# Matrix.net
KiCad netlist of a schematic drawn in Altium Designer
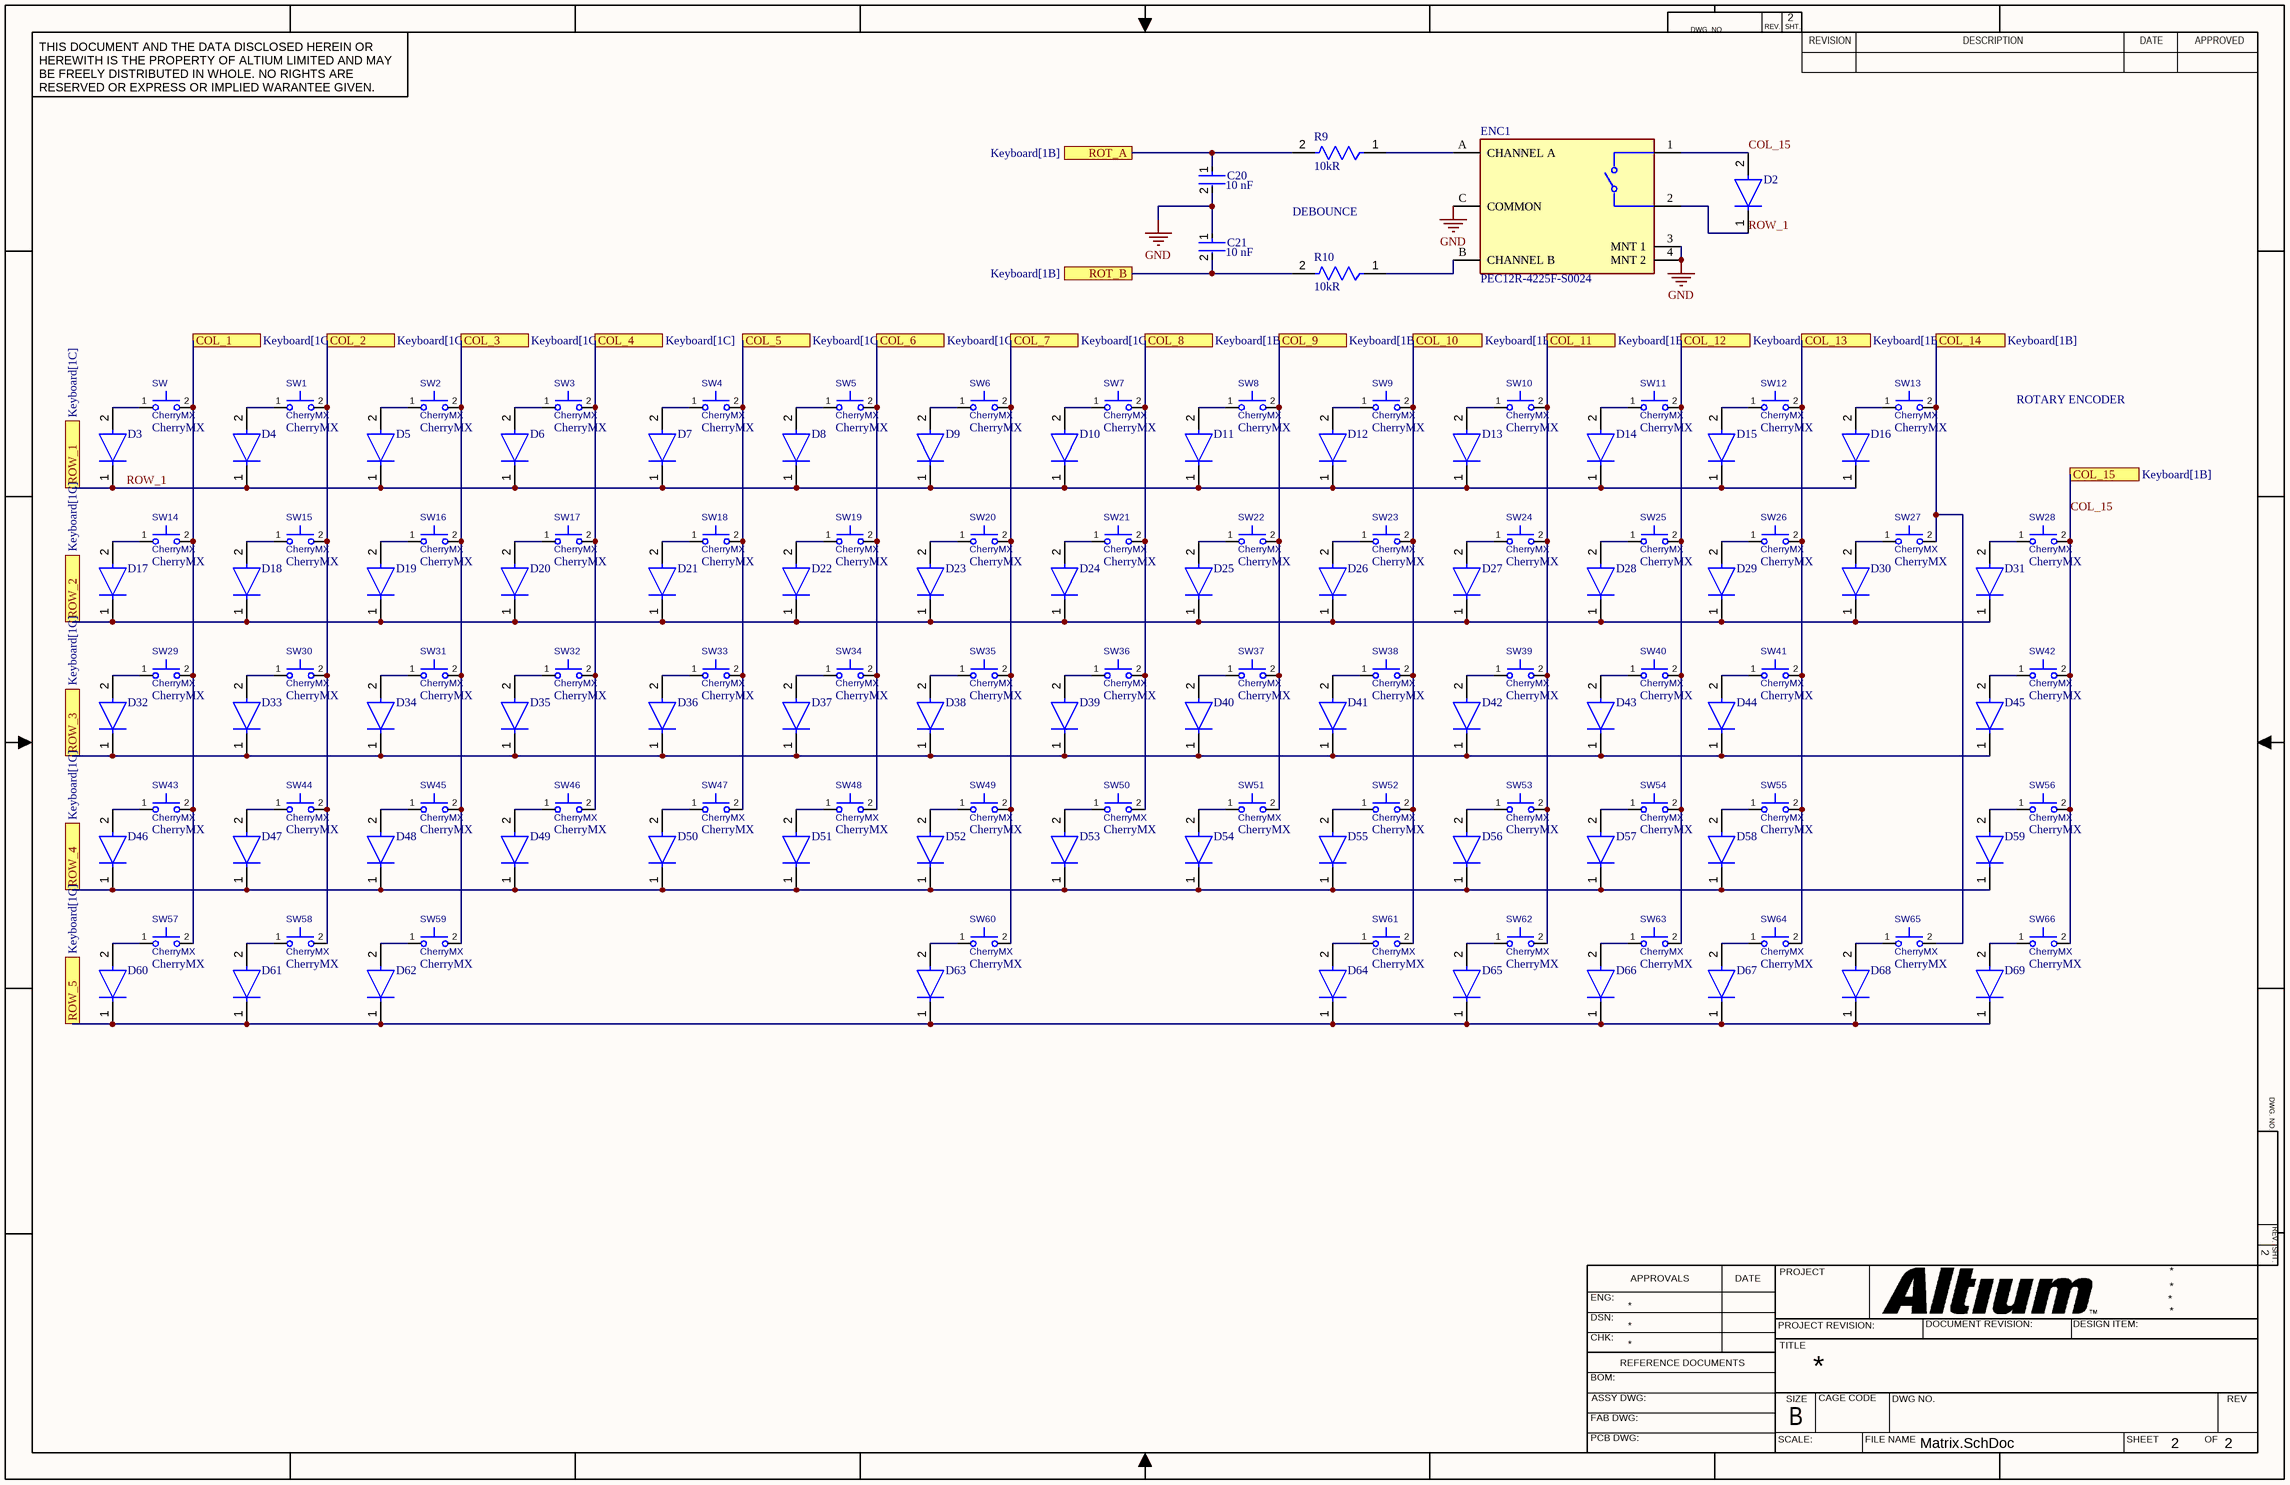
[diagram p0: Matrix.SchDoc]

(export (version "E")
  (design (tool "Eeschema 10.0.6"))
  (components
    (comp (ref "C20")
      (value "CC0603KRX7R9BB103")
      (footprint "FP-CC0603-DA-MFG")
      (description "CAP CER 10000PF 50V X7R 0603")
      (fields
        (field (name "TOLERANCE") "0.1")
        (field (name "MANUFACTURER") "YAGEO")
        (field (name "CAPACITANCE") "10 nF")
      )
      (libsource (lib "Altium Content Vault") (part "11868f565c42a9108669ba33697ecf6"))
    )
    (comp (ref "C21")
      (value "CC0603KRX7R9BB103")
      (footprint "FP-CC0603-DA-MFG")
      (description "CAP CER 10000PF 50V X7R 0603")
      (fields
        (field (name "TOLERANCE") "0.1")
        (field (name "MANUFACTURER") "YAGEO")
        (field (name "CAPACITANCE") "10 nF")
      )
      (libsource (lib "Altium Content Vault") (part "11868f565c42a9108669ba33697ecf6"))
    )
    (comp (ref "D2")
      (value "1N4148W-TP")
      (footprint "FP-SOD-123-IPC_A")
      (description "DIODE GEN PURP 100V 150MA SOD123")
      (libsource (lib "Altium Content Vault") (part "d7152d700b627762746794eb795d46e"))
    )
    (comp (ref "D3")
      (value "1N4148W-TP")
      (footprint "FP-SOD-123-IPC_A")
      (description "DIODE GEN PURP 100V 150MA SOD123")
      (libsource (lib "Altium Content Vault") (part "d7152d700b627762746794eb795d46e"))
    )
    (comp (ref "D4")
      (value "1N4148W-TP")
      (footprint "FP-SOD-123-IPC_A")
      (description "DIODE GEN PURP 100V 150MA SOD123")
      (libsource (lib "Altium Content Vault") (part "d7152d700b627762746794eb795d46e"))
    )
    (comp (ref "D5")
      (value "1N4148W-TP")
      (footprint "FP-SOD-123-IPC_A")
      (description "DIODE GEN PURP 100V 150MA SOD123")
      (libsource (lib "Altium Content Vault") (part "d7152d700b627762746794eb795d46e"))
    )
    (comp (ref "D6")
      (value "1N4148W-TP")
      (footprint "FP-SOD-123-IPC_A")
      (description "DIODE GEN PURP 100V 150MA SOD123")
      (libsource (lib "Altium Content Vault") (part "d7152d700b627762746794eb795d46e"))
    )
    (comp (ref "D7")
      (value "1N4148W-TP")
      (footprint "FP-SOD-123-IPC_A")
      (description "DIODE GEN PURP 100V 150MA SOD123")
      (libsource (lib "Altium Content Vault") (part "d7152d700b627762746794eb795d46e"))
    )
    (comp (ref "D8")
      (value "1N4148W-TP")
      (footprint "FP-SOD-123-IPC_A")
      (description "DIODE GEN PURP 100V 150MA SOD123")
      (libsource (lib "Altium Content Vault") (part "d7152d700b627762746794eb795d46e"))
    )
    (comp (ref "D9")
      (value "1N4148W-TP")
      (footprint "FP-SOD-123-IPC_A")
      (description "DIODE GEN PURP 100V 150MA SOD123")
      (libsource (lib "Altium Content Vault") (part "d7152d700b627762746794eb795d46e"))
    )
    (comp (ref "D10")
      (value "1N4148W-TP")
      (footprint "FP-SOD-123-IPC_A")
      (description "DIODE GEN PURP 100V 150MA SOD123")
      (libsource (lib "Altium Content Vault") (part "d7152d700b627762746794eb795d46e"))
    )
    (comp (ref "D11")
      (value "1N4148W-TP")
      (footprint "FP-SOD-123-IPC_A")
      (description "DIODE GEN PURP 100V 150MA SOD123")
      (libsource (lib "Altium Content Vault") (part "d7152d700b627762746794eb795d46e"))
    )
    (comp (ref "D12")
      (value "1N4148W-TP")
      (footprint "FP-SOD-123-IPC_A")
      (description "DIODE GEN PURP 100V 150MA SOD123")
      (libsource (lib "Altium Content Vault") (part "d7152d700b627762746794eb795d46e"))
    )
    (comp (ref "D13")
      (value "1N4148W-TP")
      (footprint "FP-SOD-123-IPC_A")
      (description "DIODE GEN PURP 100V 150MA SOD123")
      (libsource (lib "Altium Content Vault") (part "d7152d700b627762746794eb795d46e"))
    )
    (comp (ref "D14")
      (value "1N4148W-TP")
      (footprint "FP-SOD-123-IPC_A")
      (description "DIODE GEN PURP 100V 150MA SOD123")
      (libsource (lib "Altium Content Vault") (part "d7152d700b627762746794eb795d46e"))
    )
    (comp (ref "D15")
      (value "1N4148W-TP")
      (footprint "FP-SOD-123-IPC_A")
      (description "DIODE GEN PURP 100V 150MA SOD123")
      (libsource (lib "Altium Content Vault") (part "d7152d700b627762746794eb795d46e"))
    )
    (comp (ref "D16")
      (value "1N4148W-TP")
      (footprint "FP-SOD-123-IPC_A")
      (description "DIODE GEN PURP 100V 150MA SOD123")
      (libsource (lib "Altium Content Vault") (part "d7152d700b627762746794eb795d46e"))
    )
    (comp (ref "D17")
      (value "1N4148W-TP")
      (footprint "FP-SOD-123-IPC_A")
      (description "DIODE GEN PURP 100V 150MA SOD123")
      (libsource (lib "Altium Content Vault") (part "d7152d700b627762746794eb795d46e"))
    )
    (comp (ref "D18")
      (value "1N4148W-TP")
      (footprint "FP-SOD-123-IPC_A")
      (description "DIODE GEN PURP 100V 150MA SOD123")
      (libsource (lib "Altium Content Vault") (part "d7152d700b627762746794eb795d46e"))
    )
    (comp (ref "D19")
      (value "1N4148W-TP")
      (footprint "FP-SOD-123-IPC_A")
      (description "DIODE GEN PURP 100V 150MA SOD123")
      (libsource (lib "Altium Content Vault") (part "d7152d700b627762746794eb795d46e"))
    )
    (comp (ref "D20")
      (value "1N4148W-TP")
      (footprint "FP-SOD-123-IPC_A")
      (description "DIODE GEN PURP 100V 150MA SOD123")
      (libsource (lib "Altium Content Vault") (part "d7152d700b627762746794eb795d46e"))
    )
    (comp (ref "D21")
      (value "1N4148W-TP")
      (footprint "FP-SOD-123-IPC_A")
      (description "DIODE GEN PURP 100V 150MA SOD123")
      (libsource (lib "Altium Content Vault") (part "d7152d700b627762746794eb795d46e"))
    )
    (comp (ref "D22")
      (value "1N4148W-TP")
      (footprint "FP-SOD-123-IPC_A")
      (description "DIODE GEN PURP 100V 150MA SOD123")
      (libsource (lib "Altium Content Vault") (part "d7152d700b627762746794eb795d46e"))
    )
    (comp (ref "D23")
      (value "1N4148W-TP")
      (footprint "FP-SOD-123-IPC_A")
      (description "DIODE GEN PURP 100V 150MA SOD123")
      (libsource (lib "Altium Content Vault") (part "d7152d700b627762746794eb795d46e"))
    )
    (comp (ref "D24")
      (value "1N4148W-TP")
      (footprint "FP-SOD-123-IPC_A")
      (description "DIODE GEN PURP 100V 150MA SOD123")
      (libsource (lib "Altium Content Vault") (part "d7152d700b627762746794eb795d46e"))
    )
    (comp (ref "D25")
      (value "1N4148W-TP")
      (footprint "FP-SOD-123-IPC_A")
      (description "DIODE GEN PURP 100V 150MA SOD123")
      (libsource (lib "Altium Content Vault") (part "d7152d700b627762746794eb795d46e"))
    )
    (comp (ref "D26")
      (value "1N4148W-TP")
      (footprint "FP-SOD-123-IPC_A")
      (description "DIODE GEN PURP 100V 150MA SOD123")
      (libsource (lib "Altium Content Vault") (part "d7152d700b627762746794eb795d46e"))
    )
    (comp (ref "D27")
      (value "1N4148W-TP")
      (footprint "FP-SOD-123-IPC_A")
      (description "DIODE GEN PURP 100V 150MA SOD123")
      (libsource (lib "Altium Content Vault") (part "d7152d700b627762746794eb795d46e"))
    )
    (comp (ref "D28")
      (value "1N4148W-TP")
      (footprint "FP-SOD-123-IPC_A")
      (description "DIODE GEN PURP 100V 150MA SOD123")
      (libsource (lib "Altium Content Vault") (part "d7152d700b627762746794eb795d46e"))
    )
    (comp (ref "D29")
      (value "1N4148W-TP")
      (footprint "FP-SOD-123-IPC_A")
      (description "DIODE GEN PURP 100V 150MA SOD123")
      (libsource (lib "Altium Content Vault") (part "d7152d700b627762746794eb795d46e"))
    )
    (comp (ref "D30")
      (value "1N4148W-TP")
      (footprint "FP-SOD-123-IPC_A")
      (description "DIODE GEN PURP 100V 150MA SOD123")
      (libsource (lib "Altium Content Vault") (part "d7152d700b627762746794eb795d46e"))
    )
    (comp (ref "D31")
      (value "1N4148W-TP")
      (footprint "FP-SOD-123-IPC_A")
      (description "DIODE GEN PURP 100V 150MA SOD123")
      (libsource (lib "Altium Content Vault") (part "d7152d700b627762746794eb795d46e"))
    )
    (comp (ref "D32")
      (value "1N4148W-TP")
      (footprint "FP-SOD-123-IPC_A")
      (description "DIODE GEN PURP 100V 150MA SOD123")
      (libsource (lib "Altium Content Vault") (part "d7152d700b627762746794eb795d46e"))
    )
    (comp (ref "D33")
      (value "1N4148W-TP")
      (footprint "FP-SOD-123-IPC_A")
      (description "DIODE GEN PURP 100V 150MA SOD123")
      (libsource (lib "Altium Content Vault") (part "d7152d700b627762746794eb795d46e"))
    )
    (comp (ref "D34")
      (value "1N4148W-TP")
      (footprint "FP-SOD-123-IPC_A")
      (description "DIODE GEN PURP 100V 150MA SOD123")
      (libsource (lib "Altium Content Vault") (part "d7152d700b627762746794eb795d46e"))
    )
    (comp (ref "D35")
      (value "1N4148W-TP")
      (footprint "FP-SOD-123-IPC_A")
      (description "DIODE GEN PURP 100V 150MA SOD123")
      (libsource (lib "Altium Content Vault") (part "d7152d700b627762746794eb795d46e"))
    )
    (comp (ref "D36")
      (value "1N4148W-TP")
      (footprint "FP-SOD-123-IPC_A")
      (description "DIODE GEN PURP 100V 150MA SOD123")
      (libsource (lib "Altium Content Vault") (part "d7152d700b627762746794eb795d46e"))
    )
    (comp (ref "D37")
      (value "1N4148W-TP")
      (footprint "FP-SOD-123-IPC_A")
      (description "DIODE GEN PURP 100V 150MA SOD123")
      (libsource (lib "Altium Content Vault") (part "d7152d700b627762746794eb795d46e"))
    )
    (comp (ref "D38")
      (value "1N4148W-TP")
      (footprint "FP-SOD-123-IPC_A")
      (description "DIODE GEN PURP 100V 150MA SOD123")
      (libsource (lib "Altium Content Vault") (part "d7152d700b627762746794eb795d46e"))
    )
    (comp (ref "D39")
      (value "1N4148W-TP")
      (footprint "FP-SOD-123-IPC_A")
      (description "DIODE GEN PURP 100V 150MA SOD123")
      (libsource (lib "Altium Content Vault") (part "d7152d700b627762746794eb795d46e"))
    )
    (comp (ref "D40")
      (value "1N4148W-TP")
      (footprint "FP-SOD-123-IPC_A")
      (description "DIODE GEN PURP 100V 150MA SOD123")
      (libsource (lib "Altium Content Vault") (part "d7152d700b627762746794eb795d46e"))
    )
    (comp (ref "D41")
      (value "1N4148W-TP")
      (footprint "FP-SOD-123-IPC_A")
      (description "DIODE GEN PURP 100V 150MA SOD123")
      (libsource (lib "Altium Content Vault") (part "d7152d700b627762746794eb795d46e"))
    )
    (comp (ref "D42")
      (value "1N4148W-TP")
      (footprint "FP-SOD-123-IPC_A")
      (description "DIODE GEN PURP 100V 150MA SOD123")
      (libsource (lib "Altium Content Vault") (part "d7152d700b627762746794eb795d46e"))
    )
    (comp (ref "D43")
      (value "1N4148W-TP")
      (footprint "FP-SOD-123-IPC_A")
      (description "DIODE GEN PURP 100V 150MA SOD123")
      (libsource (lib "Altium Content Vault") (part "d7152d700b627762746794eb795d46e"))
    )
    (comp (ref "D44")
      (value "1N4148W-TP")
      (footprint "FP-SOD-123-IPC_A")
      (description "DIODE GEN PURP 100V 150MA SOD123")
      (libsource (lib "Altium Content Vault") (part "d7152d700b627762746794eb795d46e"))
    )
    (comp (ref "D45")
      (value "1N4148W-TP")
      (footprint "FP-SOD-123-IPC_A")
      (description "DIODE GEN PURP 100V 150MA SOD123")
      (libsource (lib "Altium Content Vault") (part "d7152d700b627762746794eb795d46e"))
    )
    (comp (ref "D46")
      (value "1N4148W-TP")
      (footprint "FP-SOD-123-IPC_A")
      (description "DIODE GEN PURP 100V 150MA SOD123")
      (libsource (lib "Altium Content Vault") (part "d7152d700b627762746794eb795d46e"))
    )
    (comp (ref "D47")
      (value "1N4148W-TP")
      (footprint "FP-SOD-123-IPC_A")
      (description "DIODE GEN PURP 100V 150MA SOD123")
      (libsource (lib "Altium Content Vault") (part "d7152d700b627762746794eb795d46e"))
    )
    (comp (ref "D48")
      (value "1N4148W-TP")
      (footprint "FP-SOD-123-IPC_A")
      (description "DIODE GEN PURP 100V 150MA SOD123")
      (libsource (lib "Altium Content Vault") (part "d7152d700b627762746794eb795d46e"))
    )
    (comp (ref "D49")
      (value "1N4148W-TP")
      (footprint "FP-SOD-123-IPC_A")
      (description "DIODE GEN PURP 100V 150MA SOD123")
      (libsource (lib "Altium Content Vault") (part "d7152d700b627762746794eb795d46e"))
    )
    (comp (ref "D50")
      (value "1N4148W-TP")
      (footprint "FP-SOD-123-IPC_A")
      (description "DIODE GEN PURP 100V 150MA SOD123")
      (libsource (lib "Altium Content Vault") (part "d7152d700b627762746794eb795d46e"))
    )
    (comp (ref "D51")
      (value "1N4148W-TP")
      (footprint "FP-SOD-123-IPC_A")
      (description "DIODE GEN PURP 100V 150MA SOD123")
      (libsource (lib "Altium Content Vault") (part "d7152d700b627762746794eb795d46e"))
    )
    (comp (ref "D52")
      (value "1N4148W-TP")
      (footprint "FP-SOD-123-IPC_A")
      (description "DIODE GEN PURP 100V 150MA SOD123")
      (libsource (lib "Altium Content Vault") (part "d7152d700b627762746794eb795d46e"))
    )
    (comp (ref "D53")
      (value "1N4148W-TP")
      (footprint "FP-SOD-123-IPC_A")
      (description "DIODE GEN PURP 100V 150MA SOD123")
      (libsource (lib "Altium Content Vault") (part "d7152d700b627762746794eb795d46e"))
    )
    (comp (ref "D54")
      (value "1N4148W-TP")
      (footprint "FP-SOD-123-IPC_A")
      (description "DIODE GEN PURP 100V 150MA SOD123")
      (libsource (lib "Altium Content Vault") (part "d7152d700b627762746794eb795d46e"))
    )
    (comp (ref "D55")
      (value "1N4148W-TP")
      (footprint "FP-SOD-123-IPC_A")
      (description "DIODE GEN PURP 100V 150MA SOD123")
      (libsource (lib "Altium Content Vault") (part "d7152d700b627762746794eb795d46e"))
    )
    (comp (ref "D56")
      (value "1N4148W-TP")
      (footprint "FP-SOD-123-IPC_A")
      (description "DIODE GEN PURP 100V 150MA SOD123")
      (libsource (lib "Altium Content Vault") (part "d7152d700b627762746794eb795d46e"))
    )
    (comp (ref "D57")
      (value "1N4148W-TP")
      (footprint "FP-SOD-123-IPC_A")
      (description "DIODE GEN PURP 100V 150MA SOD123")
      (libsource (lib "Altium Content Vault") (part "d7152d700b627762746794eb795d46e"))
    )
    (comp (ref "D58")
      (value "1N4148W-TP")
      (footprint "FP-SOD-123-IPC_A")
      (description "DIODE GEN PURP 100V 150MA SOD123")
      (libsource (lib "Altium Content Vault") (part "d7152d700b627762746794eb795d46e"))
    )
    (comp (ref "D59")
      (value "1N4148W-TP")
      (footprint "FP-SOD-123-IPC_A")
      (description "DIODE GEN PURP 100V 150MA SOD123")
      (libsource (lib "Altium Content Vault") (part "d7152d700b627762746794eb795d46e"))
    )
    (comp (ref "D60")
      (value "1N4148W-TP")
      (footprint "FP-SOD-123-IPC_A")
      (description "DIODE GEN PURP 100V 150MA SOD123")
      (libsource (lib "Altium Content Vault") (part "d7152d700b627762746794eb795d46e"))
    )
    (comp (ref "D61")
      (value "1N4148W-TP")
      (footprint "FP-SOD-123-IPC_A")
      (description "DIODE GEN PURP 100V 150MA SOD123")
      (libsource (lib "Altium Content Vault") (part "d7152d700b627762746794eb795d46e"))
    )
    (comp (ref "D62")
      (value "1N4148W-TP")
      (footprint "FP-SOD-123-IPC_A")
      (description "DIODE GEN PURP 100V 150MA SOD123")
      (libsource (lib "Altium Content Vault") (part "d7152d700b627762746794eb795d46e"))
    )
    (comp (ref "D63")
      (value "1N4148W-TP")
      (footprint "FP-SOD-123-IPC_A")
      (description "DIODE GEN PURP 100V 150MA SOD123")
      (libsource (lib "Altium Content Vault") (part "d7152d700b627762746794eb795d46e"))
    )
    (comp (ref "D64")
      (value "1N4148W-TP")
      (footprint "FP-SOD-123-IPC_A")
      (description "DIODE GEN PURP 100V 150MA SOD123")
      (libsource (lib "Altium Content Vault") (part "d7152d700b627762746794eb795d46e"))
    )
    (comp (ref "D65")
      (value "1N4148W-TP")
      (footprint "FP-SOD-123-IPC_A")
      (description "DIODE GEN PURP 100V 150MA SOD123")
      (libsource (lib "Altium Content Vault") (part "d7152d700b627762746794eb795d46e"))
    )
    (comp (ref "D66")
      (value "1N4148W-TP")
      (footprint "FP-SOD-123-IPC_A")
      (description "DIODE GEN PURP 100V 150MA SOD123")
      (libsource (lib "Altium Content Vault") (part "d7152d700b627762746794eb795d46e"))
    )
    (comp (ref "D67")
      (value "1N4148W-TP")
      (footprint "FP-SOD-123-IPC_A")
      (description "DIODE GEN PURP 100V 150MA SOD123")
      (libsource (lib "Altium Content Vault") (part "d7152d700b627762746794eb795d46e"))
    )
    (comp (ref "D68")
      (value "1N4148W-TP")
      (footprint "FP-SOD-123-IPC_A")
      (description "DIODE GEN PURP 100V 150MA SOD123")
      (libsource (lib "Altium Content Vault") (part "d7152d700b627762746794eb795d46e"))
    )
    (comp (ref "D69")
      (value "1N4148W-TP")
      (footprint "FP-SOD-123-IPC_A")
      (description "DIODE GEN PURP 100V 150MA SOD123")
      (libsource (lib "Altium Content Vault") (part "d7152d700b627762746794eb795d46e"))
    )
    (comp (ref "ENC1")
      (value "PEC12R-4225F-S0024")
      (footprint "FP-PEC12R-4225F-S0024-MFG")
      (description "ROTARY ENCODER MECHANICAL 24PPR")
      (libsource (lib "Altium Content Vault") (part "084942c7348c54a7e5fe2df5ed54478"))
    )
    (comp (ref "R9")
      (value "RC0402JR-0710KL")
      (footprint "FP-RC0402-0_4-IPC_C")
      (description "RES 10K OHM 5% 1/16W 0402")
      (fields (field (name "RESISTANCE") "10kR") (field (name "TOLERANCE") "5%"))
      (libsource (lib "Altium Content Vault") (part "1029c3af85768c4190bb7ad29bc67b5"))
    )
    (comp (ref "R10")
      (value "RC0402JR-0710KL")
      (footprint "FP-RC0402-0_4-IPC_C")
      (description "RES 10K OHM 5% 1/16W 0402")
      (fields (field (name "RESISTANCE") "10kR") (field (name "TOLERANCE") "5%"))
      (libsource (lib "Altium Content Vault") (part "1029c3af85768c4190bb7ad29bc67b5"))
    )
    (comp (ref "SW")
      (value "CherryMX")
      (footprint "CherryMX-Footprint-1")
      (description "Cherry Switch 1U")
      (fields (field (name "ALTIUM_VALUE") "CherryMX"))
      (libsource (lib "Brian Tan") (part "CherryMX"))
    )
    (comp (ref "SW1")
      (value "CherryMX")
      (footprint "CherryMX-Footprint-1")
      (description "Cherry Switch 1U")
      (fields (field (name "ALTIUM_VALUE") "CherryMX"))
      (libsource (lib "Brian Tan") (part "CherryMX"))
    )
    (comp (ref "SW2")
      (value "CherryMX")
      (footprint "CherryMX-Footprint-1")
      (description "Cherry Switch 1U")
      (fields (field (name "ALTIUM_VALUE") "CherryMX"))
      (libsource (lib "Brian Tan") (part "CherryMX"))
    )
    (comp (ref "SW3")
      (value "CherryMX")
      (footprint "CherryMX-Footprint-1")
      (description "Cherry Switch 1U")
      (fields (field (name "ALTIUM_VALUE") "CherryMX"))
      (libsource (lib "Brian Tan") (part "CherryMX"))
    )
    (comp (ref "SW4")
      (value "CherryMX")
      (footprint "CherryMX-Footprint-1")
      (description "Cherry Switch 1U")
      (fields (field (name "ALTIUM_VALUE") "CherryMX"))
      (libsource (lib "Brian Tan") (part "CherryMX"))
    )
    (comp (ref "SW5")
      (value "CherryMX")
      (footprint "CherryMX-Footprint-1")
      (description "Cherry Switch 1U")
      (fields (field (name "ALTIUM_VALUE") "CherryMX"))
      (libsource (lib "Brian Tan") (part "CherryMX"))
    )
    (comp (ref "SW6")
      (value "CherryMX")
      (footprint "CherryMX-Footprint-1")
      (description "Cherry Switch 1U")
      (fields (field (name "ALTIUM_VALUE") "CherryMX"))
      (libsource (lib "Brian Tan") (part "CherryMX"))
    )
    (comp (ref "SW7")
      (value "CherryMX")
      (footprint "CherryMX-Footprint-1")
      (description "Cherry Switch 1U")
      (fields (field (name "ALTIUM_VALUE") "CherryMX"))
      (libsource (lib "Brian Tan") (part "CherryMX"))
    )
    (comp (ref "SW8")
      (value "CherryMX")
      (footprint "CherryMX-Footprint-1")
      (description "Cherry Switch 1U")
      (fields (field (name "ALTIUM_VALUE") "CherryMX"))
      (libsource (lib "Brian Tan") (part "CherryMX"))
    )
    (comp (ref "SW9")
      (value "CherryMX")
      (footprint "CherryMX-Footprint-1")
      (description "Cherry Switch 1U")
      (fields (field (name "ALTIUM_VALUE") "CherryMX"))
      (libsource (lib "Brian Tan") (part "CherryMX"))
    )
    (comp (ref "SW10")
      (value "CherryMX")
      (footprint "CherryMX-Footprint-1")
      (description "Cherry Switch 1U")
      (fields (field (name "ALTIUM_VALUE") "CherryMX"))
      (libsource (lib "Brian Tan") (part "CherryMX"))
    )
    (comp (ref "SW11")
      (value "CherryMX")
      (footprint "CherryMX-Footprint-1")
      (description "Cherry Switch 1U")
      (fields (field (name "ALTIUM_VALUE") "CherryMX"))
      (libsource (lib "Brian Tan") (part "CherryMX"))
    )
    (comp (ref "SW12")
      (value "CherryMX")
      (footprint "CherryMX-Footprint-1")
      (description "Cherry Switch 1U")
      (fields (field (name "ALTIUM_VALUE") "CherryMX"))
      (libsource (lib "Brian Tan") (part "CherryMX"))
    )
    (comp (ref "SW13")
      (value "CherryMX")
      (footprint "CherryMX-Footprint-1")
      (description "Cherry Switch 1U")
      (fields (field (name "ALTIUM_VALUE") "CherryMX"))
      (libsource (lib "Brian Tan") (part "CherryMX"))
    )
    (comp (ref "SW14")
      (value "CherryMX")
      (footprint "CherryMX-Footprint-1")
      (description "Cherry Switch 1U")
      (fields (field (name "ALTIUM_VALUE") "CherryMX"))
      (libsource (lib "Brian Tan") (part "CherryMX"))
    )
    (comp (ref "SW15")
      (value "CherryMX")
      (footprint "CherryMX-Footprint-1")
      (description "Cherry Switch 1U")
      (fields (field (name "ALTIUM_VALUE") "CherryMX"))
      (libsource (lib "Brian Tan") (part "CherryMX"))
    )
    (comp (ref "SW16")
      (value "CherryMX")
      (footprint "CherryMX-Footprint-1")
      (description "Cherry Switch 1U")
      (fields (field (name "ALTIUM_VALUE") "CherryMX"))
      (libsource (lib "Brian Tan") (part "CherryMX"))
    )
    (comp (ref "SW17")
      (value "CherryMX")
      (footprint "CherryMX-Footprint-1")
      (description "Cherry Switch 1U")
      (fields (field (name "ALTIUM_VALUE") "CherryMX"))
      (libsource (lib "Brian Tan") (part "CherryMX"))
    )
    (comp (ref "SW18")
      (value "CherryMX")
      (footprint "CherryMX-Footprint-1")
      (description "Cherry Switch 1U")
      (fields (field (name "ALTIUM_VALUE") "CherryMX"))
      (libsource (lib "Brian Tan") (part "CherryMX"))
    )
    (comp (ref "SW19")
      (value "CherryMX")
      (footprint "CherryMX-Footprint-1")
      (description "Cherry Switch 1U")
      (fields (field (name "ALTIUM_VALUE") "CherryMX"))
      (libsource (lib "Brian Tan") (part "CherryMX"))
    )
    (comp (ref "SW20")
      (value "CherryMX")
      (footprint "CherryMX-Footprint-1")
      (description "Cherry Switch 1U")
      (fields (field (name "ALTIUM_VALUE") "CherryMX"))
      (libsource (lib "Brian Tan") (part "CherryMX"))
    )
    (comp (ref "SW21")
      (value "CherryMX")
      (footprint "CherryMX-Footprint-1")
      (description "Cherry Switch 1U")
      (fields (field (name "ALTIUM_VALUE") "CherryMX"))
      (libsource (lib "Brian Tan") (part "CherryMX"))
    )
    (comp (ref "SW22")
      (value "CherryMX")
      (footprint "CherryMX-Footprint-1")
      (description "Cherry Switch 1U")
      (fields (field (name "ALTIUM_VALUE") "CherryMX"))
      (libsource (lib "Brian Tan") (part "CherryMX"))
    )
    (comp (ref "SW23")
      (value "CherryMX")
      (footprint "CherryMX-Footprint-1")
      (description "Cherry Switch 1U")
      (fields (field (name "ALTIUM_VALUE") "CherryMX"))
      (libsource (lib "Brian Tan") (part "CherryMX"))
    )
    (comp (ref "SW24")
      (value "CherryMX")
      (footprint "CherryMX-Footprint-1")
      (description "Cherry Switch 1U")
      (fields (field (name "ALTIUM_VALUE") "CherryMX"))
      (libsource (lib "Brian Tan") (part "CherryMX"))
    )
    (comp (ref "SW25")
      (value "CherryMX")
      (footprint "CherryMX-Footprint-1")
      (description "Cherry Switch 1U")
      (fields (field (name "ALTIUM_VALUE") "CherryMX"))
      (libsource (lib "Brian Tan") (part "CherryMX"))
    )
    (comp (ref "SW26")
      (value "CherryMX")
      (footprint "CherryMX-Footprint-1")
      (description "Cherry Switch 1U")
      (fields (field (name "ALTIUM_VALUE") "CherryMX"))
      (libsource (lib "Brian Tan") (part "CherryMX"))
    )
    (comp (ref "SW27")
      (value "CherryMX")
      (footprint "CherryMX-Footprint-1")
      (description "Cherry Switch 1U")
      (fields (field (name "ALTIUM_VALUE") "CherryMX"))
      (libsource (lib "Brian Tan") (part "CherryMX"))
    )
    (comp (ref "SW28")
      (value "CherryMX")
      (footprint "CherryMX-Footprint-1")
      (description "Cherry Switch 1U")
      (fields (field (name "ALTIUM_VALUE") "CherryMX"))
      (libsource (lib "Brian Tan") (part "CherryMX"))
    )
    (comp (ref "SW29")
      (value "CherryMX")
      (footprint "CherryMX-Footprint-1")
      (description "Cherry Switch 1U")
      (fields (field (name "ALTIUM_VALUE") "CherryMX"))
      (libsource (lib "Brian Tan") (part "CherryMX"))
    )
    (comp (ref "SW30")
      (value "CherryMX")
      (footprint "CherryMX-Footprint-1")
      (description "Cherry Switch 1U")
      (fields (field (name "ALTIUM_VALUE") "CherryMX"))
      (libsource (lib "Brian Tan") (part "CherryMX"))
    )
    (comp (ref "SW31")
      (value "CherryMX")
      (footprint "CherryMX-Footprint-1")
      (description "Cherry Switch 1U")
      (fields (field (name "ALTIUM_VALUE") "CherryMX"))
      (libsource (lib "Brian Tan") (part "CherryMX"))
    )
    (comp (ref "SW32")
      (value "CherryMX")
      (footprint "CherryMX-Footprint-1")
      (description "Cherry Switch 1U")
      (fields (field (name "ALTIUM_VALUE") "CherryMX"))
      (libsource (lib "Brian Tan") (part "CherryMX"))
    )
    (comp (ref "SW33")
      (value "CherryMX")
      (footprint "CherryMX-Footprint-1")
      (description "Cherry Switch 1U")
      (fields (field (name "ALTIUM_VALUE") "CherryMX"))
      (libsource (lib "Brian Tan") (part "CherryMX"))
    )
    (comp (ref "SW34")
      (value "CherryMX")
      (footprint "CherryMX-Footprint-1")
      (description "Cherry Switch 1U")
      (fields (field (name "ALTIUM_VALUE") "CherryMX"))
      (libsource (lib "Brian Tan") (part "CherryMX"))
    )
    (comp (ref "SW35")
      (value "CherryMX")
      (footprint "CherryMX-Footprint-1")
      (description "Cherry Switch 1U")
      (fields (field (name "ALTIUM_VALUE") "CherryMX"))
      (libsource (lib "Brian Tan") (part "CherryMX"))
    )
    (comp (ref "SW36")
      (value "CherryMX")
      (footprint "CherryMX-Footprint-1")
      (description "Cherry Switch 1U")
      (fields (field (name "ALTIUM_VALUE") "CherryMX"))
      (libsource (lib "Brian Tan") (part "CherryMX"))
    )
    (comp (ref "SW37")
      (value "CherryMX")
      (footprint "CherryMX-Footprint-1")
      (description "Cherry Switch 1U")
      (fields (field (name "ALTIUM_VALUE") "CherryMX"))
      (libsource (lib "Brian Tan") (part "CherryMX"))
    )
    (comp (ref "SW38")
      (value "CherryMX")
      (footprint "CherryMX-Footprint-1")
      (description "Cherry Switch 1U")
      (fields (field (name "ALTIUM_VALUE") "CherryMX"))
      (libsource (lib "Brian Tan") (part "CherryMX"))
    )
    (comp (ref "SW39")
      (value "CherryMX")
      (footprint "CherryMX-Footprint-1")
      (description "Cherry Switch 1U")
      (fields (field (name "ALTIUM_VALUE") "CherryMX"))
      (libsource (lib "Brian Tan") (part "CherryMX"))
    )
    (comp (ref "SW40")
      (value "CherryMX")
      (footprint "CherryMX-Footprint-1")
      (description "Cherry Switch 1U")
      (fields (field (name "ALTIUM_VALUE") "CherryMX"))
      (libsource (lib "Brian Tan") (part "CherryMX"))
    )
    (comp (ref "SW41")
      (value "CherryMX")
      (footprint "CherryMX-Footprint-1")
      (description "Cherry Switch 1U")
      (fields (field (name "ALTIUM_VALUE") "CherryMX"))
      (libsource (lib "Brian Tan") (part "CherryMX"))
    )
    (comp (ref "SW42")
      (value "CherryMX")
      (footprint "CherryMX-Footprint-1")
      (description "Cherry Switch 1U")
      (fields (field (name "ALTIUM_VALUE") "CherryMX"))
      (libsource (lib "Brian Tan") (part "CherryMX"))
    )
    (comp (ref "SW43")
      (value "CherryMX")
      (footprint "CherryMX-Footprint-1")
      (description "Cherry Switch 1U")
      (fields (field (name "ALTIUM_VALUE") "CherryMX"))
      (libsource (lib "Brian Tan") (part "CherryMX"))
    )
    (comp (ref "SW44")
      (value "CherryMX")
      (footprint "CherryMX-Footprint-1")
      (description "Cherry Switch 1U")
      (fields (field (name "ALTIUM_VALUE") "CherryMX"))
      (libsource (lib "Brian Tan") (part "CherryMX"))
    )
    (comp (ref "SW45")
      (value "CherryMX")
      (footprint "CherryMX-Footprint-1")
      (description "Cherry Switch 1U")
      (fields (field (name "ALTIUM_VALUE") "CherryMX"))
      (libsource (lib "Brian Tan") (part "CherryMX"))
    )
    (comp (ref "SW46")
      (value "CherryMX")
      (footprint "CherryMX-Footprint-1")
      (description "Cherry Switch 1U")
      (fields (field (name "ALTIUM_VALUE") "CherryMX"))
      (libsource (lib "Brian Tan") (part "CherryMX"))
    )
    (comp (ref "SW47")
      (value "CherryMX")
      (footprint "CherryMX-Footprint-1")
      (description "Cherry Switch 1U")
      (fields (field (name "ALTIUM_VALUE") "CherryMX"))
      (libsource (lib "Brian Tan") (part "CherryMX"))
    )
    (comp (ref "SW48")
      (value "CherryMX")
      (footprint "CherryMX-Footprint-1")
      (description "Cherry Switch 1U")
      (fields (field (name "ALTIUM_VALUE") "CherryMX"))
      (libsource (lib "Brian Tan") (part "CherryMX"))
    )
    (comp (ref "SW49")
      (value "CherryMX")
      (footprint "CherryMX-Footprint-1")
      (description "Cherry Switch 1U")
      (fields (field (name "ALTIUM_VALUE") "CherryMX"))
      (libsource (lib "Brian Tan") (part "CherryMX"))
    )
    (comp (ref "SW50")
      (value "CherryMX")
      (footprint "CherryMX-Footprint-1")
      (description "Cherry Switch 1U")
      (fields (field (name "ALTIUM_VALUE") "CherryMX"))
      (libsource (lib "Brian Tan") (part "CherryMX"))
    )
    (comp (ref "SW51")
      (value "CherryMX")
      (footprint "CherryMX-Footprint-1")
      (description "Cherry Switch 1U")
      (fields (field (name "ALTIUM_VALUE") "CherryMX"))
      (libsource (lib "Brian Tan") (part "CherryMX"))
    )
    (comp (ref "SW52")
      (value "CherryMX")
      (footprint "CherryMX-Footprint-1")
      (description "Cherry Switch 1U")
      (fields (field (name "ALTIUM_VALUE") "CherryMX"))
      (libsource (lib "Brian Tan") (part "CherryMX"))
    )
    (comp (ref "SW53")
      (value "CherryMX")
      (footprint "CherryMX-Footprint-1")
      (description "Cherry Switch 1U")
      (fields (field (name "ALTIUM_VALUE") "CherryMX"))
      (libsource (lib "Brian Tan") (part "CherryMX"))
    )
    (comp (ref "SW54")
      (value "CherryMX")
      (footprint "CherryMX-Footprint-1")
      (description "Cherry Switch 1U")
      (fields (field (name "ALTIUM_VALUE") "CherryMX"))
      (libsource (lib "Brian Tan") (part "CherryMX"))
    )
    (comp (ref "SW55")
      (value "CherryMX")
      (footprint "CherryMX-Footprint-1")
      (description "Cherry Switch 1U")
      (fields (field (name "ALTIUM_VALUE") "CherryMX"))
      (libsource (lib "Brian Tan") (part "CherryMX"))
    )
    (comp (ref "SW56")
      (value "CherryMX")
      (footprint "CherryMX-Footprint-1")
      (description "Cherry Switch 1U")
      (fields (field (name "ALTIUM_VALUE") "CherryMX"))
      (libsource (lib "Brian Tan") (part "CherryMX"))
    )
    (comp (ref "SW57")
      (value "CherryMX")
      (footprint "CherryMX-Footprint-1")
      (description "Cherry Switch 1U")
      (fields (field (name "ALTIUM_VALUE") "CherryMX"))
      (libsource (lib "Brian Tan") (part "CherryMX"))
    )
    (comp (ref "SW58")
      (value "CherryMX")
      (footprint "CherryMX-Footprint-1")
      (description "Cherry Switch 1U")
      (fields (field (name "ALTIUM_VALUE") "CherryMX"))
      (libsource (lib "Brian Tan") (part "CherryMX"))
    )
    (comp (ref "SW59")
      (value "CherryMX")
      (footprint "CherryMX-Footprint-1")
      (description "Cherry Switch 1U")
      (fields (field (name "ALTIUM_VALUE") "CherryMX"))
      (libsource (lib "Brian Tan") (part "CherryMX"))
    )
    (comp (ref "SW60")
      (value "CherryMX")
      (footprint "CherryMX-Footprint-1")
      (description "Cherry Switch 1U")
      (fields (field (name "ALTIUM_VALUE") "CherryMX"))
      (libsource (lib "Brian Tan") (part "CherryMX"))
    )
    (comp (ref "SW61")
      (value "CherryMX")
      (footprint "CherryMX-Footprint-1")
      (description "Cherry Switch 1U")
      (fields (field (name "ALTIUM_VALUE") "CherryMX"))
      (libsource (lib "Brian Tan") (part "CherryMX"))
    )
    (comp (ref "SW62")
      (value "CherryMX")
      (footprint "CherryMX-Footprint-1")
      (description "Cherry Switch 1U")
      (fields (field (name "ALTIUM_VALUE") "CherryMX"))
      (libsource (lib "Brian Tan") (part "CherryMX"))
    )
    (comp (ref "SW63")
      (value "CherryMX")
      (footprint "CherryMX-Footprint-1")
      (description "Cherry Switch 1U")
      (fields (field (name "ALTIUM_VALUE") "CherryMX"))
      (libsource (lib "Brian Tan") (part "CherryMX"))
    )
    (comp (ref "SW64")
      (value "CherryMX")
      (footprint "CherryMX-Footprint-1")
      (description "Cherry Switch 1U")
      (fields (field (name "ALTIUM_VALUE") "CherryMX"))
      (libsource (lib "Brian Tan") (part "CherryMX"))
    )
    (comp (ref "SW65")
      (value "CherryMX")
      (footprint "CherryMX-Footprint-1")
      (description "Cherry Switch 1U")
      (fields (field (name "ALTIUM_VALUE") "CherryMX"))
      (libsource (lib "Brian Tan") (part "CherryMX"))
    )
    (comp (ref "SW66")
      (value "CherryMX")
      (footprint "CherryMX-Footprint-1")
      (description "Cherry Switch 1U")
      (fields (field (name "ALTIUM_VALUE") "CherryMX"))
      (libsource (lib "Brian Tan") (part "CherryMX"))
    )
  )
  (nets
    (net (code "1") (name "/COL_1") (class "Default")
      (node (ref "SW") (pin "2") (pinfunction "2_2") (pintype "passive"))
      (node (ref "SW14") (pin "2") (pinfunction "2_2") (pintype "passive"))
      (node (ref "SW29") (pin "2") (pinfunction "2_2") (pintype "passive"))
      (node (ref "SW43") (pin "2") (pinfunction "2_2") (pintype "passive"))
      (node (ref "SW57") (pin "2") (pinfunction "2_2") (pintype "passive"))
    )
    (net (code "2") (name "/COL_2") (class "Default")
      (node (ref "SW1") (pin "2") (pinfunction "2_2") (pintype "passive"))
      (node (ref "SW15") (pin "2") (pinfunction "2_2") (pintype "passive"))
      (node (ref "SW30") (pin "2") (pinfunction "2_2") (pintype "passive"))
      (node (ref "SW44") (pin "2") (pinfunction "2_2") (pintype "passive"))
      (node (ref "SW58") (pin "2") (pinfunction "2_2") (pintype "passive"))
    )
    (net (code "3") (name "/COL_3") (class "Default")
      (node (ref "SW16") (pin "2") (pinfunction "2_2") (pintype "passive"))
      (node (ref "SW2") (pin "2") (pinfunction "2_2") (pintype "passive"))
      (node (ref "SW31") (pin "2") (pinfunction "2_2") (pintype "passive"))
      (node (ref "SW45") (pin "2") (pinfunction "2_2") (pintype "passive"))
      (node (ref "SW59") (pin "2") (pinfunction "2_2") (pintype "passive"))
    )
    (net (code "4") (name "/COL_4") (class "Default")
      (node (ref "SW17") (pin "2") (pinfunction "2_2") (pintype "passive"))
      (node (ref "SW3") (pin "2") (pinfunction "2_2") (pintype "passive"))
      (node (ref "SW32") (pin "2") (pinfunction "2_2") (pintype "passive"))
      (node (ref "SW46") (pin "2") (pinfunction "2_2") (pintype "passive"))
    )
    (net (code "5") (name "/COL_5") (class "Default")
      (node (ref "SW18") (pin "2") (pinfunction "2_2") (pintype "passive"))
      (node (ref "SW33") (pin "2") (pinfunction "2_2") (pintype "passive"))
      (node (ref "SW4") (pin "2") (pinfunction "2_2") (pintype "passive"))
      (node (ref "SW47") (pin "2") (pinfunction "2_2") (pintype "passive"))
    )
    (net (code "6") (name "/COL_6") (class "Default")
      (node (ref "SW19") (pin "2") (pinfunction "2_2") (pintype "passive"))
      (node (ref "SW34") (pin "2") (pinfunction "2_2") (pintype "passive"))
      (node (ref "SW48") (pin "2") (pinfunction "2_2") (pintype "passive"))
      (node (ref "SW5") (pin "2") (pinfunction "2_2") (pintype "passive"))
    )
    (net (code "7") (name "/COL_7") (class "Default")
      (node (ref "SW20") (pin "2") (pinfunction "2_2") (pintype "passive"))
      (node (ref "SW35") (pin "2") (pinfunction "2_2") (pintype "passive"))
      (node (ref "SW49") (pin "2") (pinfunction "2_2") (pintype "passive"))
      (node (ref "SW6") (pin "2") (pinfunction "2_2") (pintype "passive"))
      (node (ref "SW60") (pin "2") (pinfunction "2_2") (pintype "passive"))
    )
    (net (code "8") (name "/COL_8") (class "Default")
      (node (ref "SW21") (pin "2") (pinfunction "2_2") (pintype "passive"))
      (node (ref "SW36") (pin "2") (pinfunction "2_2") (pintype "passive"))
      (node (ref "SW50") (pin "2") (pinfunction "2_2") (pintype "passive"))
      (node (ref "SW7") (pin "2") (pinfunction "2_2") (pintype "passive"))
    )
    (net (code "9") (name "/COL_9") (class "Default")
      (node (ref "SW22") (pin "2") (pinfunction "2_2") (pintype "passive"))
      (node (ref "SW37") (pin "2") (pinfunction "2_2") (pintype "passive"))
      (node (ref "SW51") (pin "2") (pinfunction "2_2") (pintype "passive"))
      (node (ref "SW8") (pin "2") (pinfunction "2_2") (pintype "passive"))
    )
    (net (code "10") (name "/COL_10") (class "Default")
      (node (ref "SW23") (pin "2") (pinfunction "2_2") (pintype "passive"))
      (node (ref "SW38") (pin "2") (pinfunction "2_2") (pintype "passive"))
      (node (ref "SW52") (pin "2") (pinfunction "2_2") (pintype "passive"))
      (node (ref "SW61") (pin "2") (pinfunction "2_2") (pintype "passive"))
      (node (ref "SW9") (pin "2") (pinfunction "2_2") (pintype "passive"))
    )
    (net (code "11") (name "/COL_11") (class "Default")
      (node (ref "SW10") (pin "2") (pinfunction "2_2") (pintype "passive"))
      (node (ref "SW24") (pin "2") (pinfunction "2_2") (pintype "passive"))
      (node (ref "SW39") (pin "2") (pinfunction "2_2") (pintype "passive"))
      (node (ref "SW53") (pin "2") (pinfunction "2_2") (pintype "passive"))
      (node (ref "SW62") (pin "2") (pinfunction "2_2") (pintype "passive"))
    )
    (net (code "12") (name "/COL_12") (class "Default")
      (node (ref "SW11") (pin "2") (pinfunction "2_2") (pintype "passive"))
      (node (ref "SW25") (pin "2") (pinfunction "2_2") (pintype "passive"))
      (node (ref "SW40") (pin "2") (pinfunction "2_2") (pintype "passive"))
      (node (ref "SW54") (pin "2") (pinfunction "2_2") (pintype "passive"))
      (node (ref "SW63") (pin "2") (pinfunction "2_2") (pintype "passive"))
    )
    (net (code "13") (name "/COL_13") (class "Default")
      (node (ref "SW12") (pin "2") (pinfunction "2_2") (pintype "passive"))
      (node (ref "SW26") (pin "2") (pinfunction "2_2") (pintype "passive"))
      (node (ref "SW41") (pin "2") (pinfunction "2_2") (pintype "passive"))
      (node (ref "SW55") (pin "2") (pinfunction "2_2") (pintype "passive"))
      (node (ref "SW64") (pin "2") (pinfunction "2_2") (pintype "passive"))
    )
    (net (code "14") (name "/COL_14") (class "Default")
      (node (ref "SW13") (pin "2") (pinfunction "2_2") (pintype "passive"))
      (node (ref "SW27") (pin "2") (pinfunction "2_2") (pintype "passive"))
      (node (ref "SW65") (pin "2") (pinfunction "2_2") (pintype "passive"))
    )
    (net (code "15") (name "/COL_15") (class "Default")
      (node (ref "D2") (pin "2") (pinfunction "A_2") (pintype "passive"))
      (node (ref "ENC1") (pin "1") (pinfunction "1_1") (pintype "passive"))
      (node (ref "SW28") (pin "2") (pinfunction "2_2") (pintype "passive"))
      (node (ref "SW42") (pin "2") (pinfunction "2_2") (pintype "passive"))
      (node (ref "SW56") (pin "2") (pinfunction "2_2") (pintype "passive"))
      (node (ref "SW66") (pin "2") (pinfunction "2_2") (pintype "passive"))
    )
    (net (code "16") (name "/ROT_A") (class "Default")
      (node (ref "C20") (pin "1") (pinfunction "1_1") (pintype "passive"))
      (node (ref "R9") (pin "2") (pinfunction "2_2") (pintype "passive"))
    )
    (net (code "17") (name "/ROT_B") (class "Default")
      (node (ref "C21") (pin "2") (pinfunction "2_2") (pintype "passive"))
      (node (ref "R10") (pin "2") (pinfunction "2_2") (pintype "passive"))
    )
    (net (code "18") (name "/ROW_1") (class "Default")
      (node (ref "D10") (pin "1") (pinfunction "C_1") (pintype "passive"))
      (node (ref "D11") (pin "1") (pinfunction "C_1") (pintype "passive"))
      (node (ref "D12") (pin "1") (pinfunction "C_1") (pintype "passive"))
      (node (ref "D13") (pin "1") (pinfunction "C_1") (pintype "passive"))
      (node (ref "D14") (pin "1") (pinfunction "C_1") (pintype "passive"))
      (node (ref "D15") (pin "1") (pinfunction "C_1") (pintype "passive"))
      (node (ref "D16") (pin "1") (pinfunction "C_1") (pintype "passive"))
      (node (ref "D2") (pin "1") (pinfunction "C_1") (pintype "passive"))
      (node (ref "D3") (pin "1") (pinfunction "C_1") (pintype "passive"))
      (node (ref "D4") (pin "1") (pinfunction "C_1") (pintype "passive"))
      (node (ref "D5") (pin "1") (pinfunction "C_1") (pintype "passive"))
      (node (ref "D6") (pin "1") (pinfunction "C_1") (pintype "passive"))
      (node (ref "D7") (pin "1") (pinfunction "C_1") (pintype "passive"))
      (node (ref "D8") (pin "1") (pinfunction "C_1") (pintype "passive"))
      (node (ref "D9") (pin "1") (pinfunction "C_1") (pintype "passive"))
      (node (ref "ENC1") (pin "2") (pinfunction "2_2") (pintype "passive"))
    )
    (net (code "19") (name "/ROW_2") (class "Default")
      (node (ref "D17") (pin "1") (pinfunction "C_1") (pintype "passive"))
      (node (ref "D18") (pin "1") (pinfunction "C_1") (pintype "passive"))
      (node (ref "D19") (pin "1") (pinfunction "C_1") (pintype "passive"))
      (node (ref "D20") (pin "1") (pinfunction "C_1") (pintype "passive"))
      (node (ref "D21") (pin "1") (pinfunction "C_1") (pintype "passive"))
      (node (ref "D22") (pin "1") (pinfunction "C_1") (pintype "passive"))
      (node (ref "D23") (pin "1") (pinfunction "C_1") (pintype "passive"))
      (node (ref "D24") (pin "1") (pinfunction "C_1") (pintype "passive"))
      (node (ref "D25") (pin "1") (pinfunction "C_1") (pintype "passive"))
      (node (ref "D26") (pin "1") (pinfunction "C_1") (pintype "passive"))
      (node (ref "D27") (pin "1") (pinfunction "C_1") (pintype "passive"))
      (node (ref "D28") (pin "1") (pinfunction "C_1") (pintype "passive"))
      (node (ref "D29") (pin "1") (pinfunction "C_1") (pintype "passive"))
      (node (ref "D30") (pin "1") (pinfunction "C_1") (pintype "passive"))
      (node (ref "D31") (pin "1") (pinfunction "C_1") (pintype "passive"))
    )
    (net (code "20") (name "/ROW_3") (class "Default")
      (node (ref "D32") (pin "1") (pinfunction "C_1") (pintype "passive"))
      (node (ref "D33") (pin "1") (pinfunction "C_1") (pintype "passive"))
      (node (ref "D34") (pin "1") (pinfunction "C_1") (pintype "passive"))
      (node (ref "D35") (pin "1") (pinfunction "C_1") (pintype "passive"))
      (node (ref "D36") (pin "1") (pinfunction "C_1") (pintype "passive"))
      (node (ref "D37") (pin "1") (pinfunction "C_1") (pintype "passive"))
      (node (ref "D38") (pin "1") (pinfunction "C_1") (pintype "passive"))
      (node (ref "D39") (pin "1") (pinfunction "C_1") (pintype "passive"))
      (node (ref "D40") (pin "1") (pinfunction "C_1") (pintype "passive"))
      (node (ref "D41") (pin "1") (pinfunction "C_1") (pintype "passive"))
      (node (ref "D42") (pin "1") (pinfunction "C_1") (pintype "passive"))
      (node (ref "D43") (pin "1") (pinfunction "C_1") (pintype "passive"))
      (node (ref "D44") (pin "1") (pinfunction "C_1") (pintype "passive"))
      (node (ref "D45") (pin "1") (pinfunction "C_1") (pintype "passive"))
    )
    (net (code "21") (name "/ROW_4") (class "Default")
      (node (ref "D46") (pin "1") (pinfunction "C_1") (pintype "passive"))
      (node (ref "D47") (pin "1") (pinfunction "C_1") (pintype "passive"))
      (node (ref "D48") (pin "1") (pinfunction "C_1") (pintype "passive"))
      (node (ref "D49") (pin "1") (pinfunction "C_1") (pintype "passive"))
      (node (ref "D50") (pin "1") (pinfunction "C_1") (pintype "passive"))
      (node (ref "D51") (pin "1") (pinfunction "C_1") (pintype "passive"))
      (node (ref "D52") (pin "1") (pinfunction "C_1") (pintype "passive"))
      (node (ref "D53") (pin "1") (pinfunction "C_1") (pintype "passive"))
      (node (ref "D54") (pin "1") (pinfunction "C_1") (pintype "passive"))
      (node (ref "D55") (pin "1") (pinfunction "C_1") (pintype "passive"))
      (node (ref "D56") (pin "1") (pinfunction "C_1") (pintype "passive"))
      (node (ref "D57") (pin "1") (pinfunction "C_1") (pintype "passive"))
      (node (ref "D58") (pin "1") (pinfunction "C_1") (pintype "passive"))
      (node (ref "D59") (pin "1") (pinfunction "C_1") (pintype "passive"))
    )
    (net (code "22") (name "/ROW_5") (class "Default")
      (node (ref "D60") (pin "1") (pinfunction "C_1") (pintype "passive"))
      (node (ref "D61") (pin "1") (pinfunction "C_1") (pintype "passive"))
      (node (ref "D62") (pin "1") (pinfunction "C_1") (pintype "passive"))
      (node (ref "D63") (pin "1") (pinfunction "C_1") (pintype "passive"))
      (node (ref "D64") (pin "1") (pinfunction "C_1") (pintype "passive"))
      (node (ref "D65") (pin "1") (pinfunction "C_1") (pintype "passive"))
      (node (ref "D66") (pin "1") (pinfunction "C_1") (pintype "passive"))
      (node (ref "D67") (pin "1") (pinfunction "C_1") (pintype "passive"))
      (node (ref "D68") (pin "1") (pinfunction "C_1") (pintype "passive"))
      (node (ref "D69") (pin "1") (pinfunction "C_1") (pintype "passive"))
    )
    (net (code "23") (name "GND") (class "Default")
      (node (ref "C20") (pin "2") (pinfunction "2_2") (pintype "passive"))
      (node (ref "C21") (pin "1") (pinfunction "1_1") (pintype "passive"))
      (node (ref "ENC1") (pin "3") (pinfunction "MNT_1_3") (pintype "passive"))
      (node (ref "ENC1") (pin "4") (pinfunction "MNT_2_4") (pintype "passive"))
      (node (ref "ENC1") (pin "C") (pinfunction "COMMON_C") (pintype "passive"))
    )
    (net (code "24") (name "Net-(D3-A)") (class "Default")
      (node (ref "D3") (pin "2") (pinfunction "A_2") (pintype "passive"))
      (node (ref "SW") (pin "1") (pinfunction "1_1") (pintype "passive"))
    )
    (net (code "25") (name "Net-(D4-A)") (class "Default")
      (node (ref "D4") (pin "2") (pinfunction "A_2") (pintype "passive"))
      (node (ref "SW1") (pin "1") (pinfunction "1_1") (pintype "passive"))
    )
    (net (code "26") (name "Net-(D5-A)") (class "Default")
      (node (ref "D5") (pin "2") (pinfunction "A_2") (pintype "passive"))
      (node (ref "SW2") (pin "1") (pinfunction "1_1") (pintype "passive"))
    )
    (net (code "27") (name "Net-(D6-A)") (class "Default")
      (node (ref "D6") (pin "2") (pinfunction "A_2") (pintype "passive"))
      (node (ref "SW3") (pin "1") (pinfunction "1_1") (pintype "passive"))
    )
    (net (code "28") (name "Net-(D7-A)") (class "Default")
      (node (ref "D7") (pin "2") (pinfunction "A_2") (pintype "passive"))
      (node (ref "SW4") (pin "1") (pinfunction "1_1") (pintype "passive"))
    )
    (net (code "29") (name "Net-(D8-A)") (class "Default")
      (node (ref "D8") (pin "2") (pinfunction "A_2") (pintype "passive"))
      (node (ref "SW5") (pin "1") (pinfunction "1_1") (pintype "passive"))
    )
    (net (code "30") (name "Net-(D9-A)") (class "Default")
      (node (ref "D9") (pin "2") (pinfunction "A_2") (pintype "passive"))
      (node (ref "SW6") (pin "1") (pinfunction "1_1") (pintype "passive"))
    )
    (net (code "31") (name "Net-(D10-A)") (class "Default")
      (node (ref "D10") (pin "2") (pinfunction "A_2") (pintype "passive"))
      (node (ref "SW7") (pin "1") (pinfunction "1_1") (pintype "passive"))
    )
    (net (code "32") (name "Net-(D11-A)") (class "Default")
      (node (ref "D11") (pin "2") (pinfunction "A_2") (pintype "passive"))
      (node (ref "SW8") (pin "1") (pinfunction "1_1") (pintype "passive"))
    )
    (net (code "33") (name "Net-(D12-A)") (class "Default")
      (node (ref "D12") (pin "2") (pinfunction "A_2") (pintype "passive"))
      (node (ref "SW9") (pin "1") (pinfunction "1_1") (pintype "passive"))
    )
    (net (code "34") (name "Net-(D13-A)") (class "Default")
      (node (ref "D13") (pin "2") (pinfunction "A_2") (pintype "passive"))
      (node (ref "SW10") (pin "1") (pinfunction "1_1") (pintype "passive"))
    )
    (net (code "35") (name "Net-(D14-A)") (class "Default")
      (node (ref "D14") (pin "2") (pinfunction "A_2") (pintype "passive"))
      (node (ref "SW11") (pin "1") (pinfunction "1_1") (pintype "passive"))
    )
    (net (code "36") (name "Net-(D15-A)") (class "Default")
      (node (ref "D15") (pin "2") (pinfunction "A_2") (pintype "passive"))
      (node (ref "SW12") (pin "1") (pinfunction "1_1") (pintype "passive"))
    )
    (net (code "37") (name "Net-(D16-A)") (class "Default")
      (node (ref "D16") (pin "2") (pinfunction "A_2") (pintype "passive"))
      (node (ref "SW13") (pin "1") (pinfunction "1_1") (pintype "passive"))
    )
    (net (code "38") (name "Net-(D17-A)") (class "Default")
      (node (ref "D17") (pin "2") (pinfunction "A_2") (pintype "passive"))
      (node (ref "SW14") (pin "1") (pinfunction "1_1") (pintype "passive"))
    )
    (net (code "39") (name "Net-(D18-A)") (class "Default")
      (node (ref "D18") (pin "2") (pinfunction "A_2") (pintype "passive"))
      (node (ref "SW15") (pin "1") (pinfunction "1_1") (pintype "passive"))
    )
    (net (code "40") (name "Net-(D19-A)") (class "Default")
      (node (ref "D19") (pin "2") (pinfunction "A_2") (pintype "passive"))
      (node (ref "SW16") (pin "1") (pinfunction "1_1") (pintype "passive"))
    )
    (net (code "41") (name "Net-(D20-A)") (class "Default")
      (node (ref "D20") (pin "2") (pinfunction "A_2") (pintype "passive"))
      (node (ref "SW17") (pin "1") (pinfunction "1_1") (pintype "passive"))
    )
    (net (code "42") (name "Net-(D21-A)") (class "Default")
      (node (ref "D21") (pin "2") (pinfunction "A_2") (pintype "passive"))
      (node (ref "SW18") (pin "1") (pinfunction "1_1") (pintype "passive"))
    )
    (net (code "43") (name "Net-(D22-A)") (class "Default")
      (node (ref "D22") (pin "2") (pinfunction "A_2") (pintype "passive"))
      (node (ref "SW19") (pin "1") (pinfunction "1_1") (pintype "passive"))
    )
    (net (code "44") (name "Net-(D23-A)") (class "Default")
      (node (ref "D23") (pin "2") (pinfunction "A_2") (pintype "passive"))
      (node (ref "SW20") (pin "1") (pinfunction "1_1") (pintype "passive"))
    )
    (net (code "45") (name "Net-(D24-A)") (class "Default")
      (node (ref "D24") (pin "2") (pinfunction "A_2") (pintype "passive"))
      (node (ref "SW21") (pin "1") (pinfunction "1_1") (pintype "passive"))
    )
    (net (code "46") (name "Net-(D25-A)") (class "Default")
      (node (ref "D25") (pin "2") (pinfunction "A_2") (pintype "passive"))
      (node (ref "SW22") (pin "1") (pinfunction "1_1") (pintype "passive"))
    )
    (net (code "47") (name "Net-(D26-A)") (class "Default")
      (node (ref "D26") (pin "2") (pinfunction "A_2") (pintype "passive"))
      (node (ref "SW23") (pin "1") (pinfunction "1_1") (pintype "passive"))
    )
    (net (code "48") (name "Net-(D27-A)") (class "Default")
      (node (ref "D27") (pin "2") (pinfunction "A_2") (pintype "passive"))
      (node (ref "SW24") (pin "1") (pinfunction "1_1") (pintype "passive"))
    )
    (net (code "49") (name "Net-(D28-A)") (class "Default")
      (node (ref "D28") (pin "2") (pinfunction "A_2") (pintype "passive"))
      (node (ref "SW25") (pin "1") (pinfunction "1_1") (pintype "passive"))
    )
    (net (code "50") (name "Net-(D29-A)") (class "Default")
      (node (ref "D29") (pin "2") (pinfunction "A_2") (pintype "passive"))
      (node (ref "SW26") (pin "1") (pinfunction "1_1") (pintype "passive"))
    )
    (net (code "51") (name "Net-(D30-A)") (class "Default")
      (node (ref "D30") (pin "2") (pinfunction "A_2") (pintype "passive"))
      (node (ref "SW27") (pin "1") (pinfunction "1_1") (pintype "passive"))
    )
    (net (code "52") (name "Net-(D31-A)") (class "Default")
      (node (ref "D31") (pin "2") (pinfunction "A_2") (pintype "passive"))
      (node (ref "SW28") (pin "1") (pinfunction "1_1") (pintype "passive"))
    )
    (net (code "53") (name "Net-(D32-A)") (class "Default")
      (node (ref "D32") (pin "2") (pinfunction "A_2") (pintype "passive"))
      (node (ref "SW29") (pin "1") (pinfunction "1_1") (pintype "passive"))
    )
    (net (code "54") (name "Net-(D33-A)") (class "Default")
      (node (ref "D33") (pin "2") (pinfunction "A_2") (pintype "passive"))
      (node (ref "SW30") (pin "1") (pinfunction "1_1") (pintype "passive"))
    )
    (net (code "55") (name "Net-(D34-A)") (class "Default")
      (node (ref "D34") (pin "2") (pinfunction "A_2") (pintype "passive"))
      (node (ref "SW31") (pin "1") (pinfunction "1_1") (pintype "passive"))
    )
    (net (code "56") (name "Net-(D35-A)") (class "Default")
      (node (ref "D35") (pin "2") (pinfunction "A_2") (pintype "passive"))
      (node (ref "SW32") (pin "1") (pinfunction "1_1") (pintype "passive"))
    )
    (net (code "57") (name "Net-(D36-A)") (class "Default")
      (node (ref "D36") (pin "2") (pinfunction "A_2") (pintype "passive"))
      (node (ref "SW33") (pin "1") (pinfunction "1_1") (pintype "passive"))
    )
    (net (code "58") (name "Net-(D37-A)") (class "Default")
      (node (ref "D37") (pin "2") (pinfunction "A_2") (pintype "passive"))
      (node (ref "SW34") (pin "1") (pinfunction "1_1") (pintype "passive"))
    )
    (net (code "59") (name "Net-(D38-A)") (class "Default")
      (node (ref "D38") (pin "2") (pinfunction "A_2") (pintype "passive"))
      (node (ref "SW35") (pin "1") (pinfunction "1_1") (pintype "passive"))
    )
    (net (code "60") (name "Net-(D39-A)") (class "Default")
      (node (ref "D39") (pin "2") (pinfunction "A_2") (pintype "passive"))
      (node (ref "SW36") (pin "1") (pinfunction "1_1") (pintype "passive"))
    )
    (net (code "61") (name "Net-(D40-A)") (class "Default")
      (node (ref "D40") (pin "2") (pinfunction "A_2") (pintype "passive"))
      (node (ref "SW37") (pin "1") (pinfunction "1_1") (pintype "passive"))
    )
    (net (code "62") (name "Net-(D41-A)") (class "Default")
      (node (ref "D41") (pin "2") (pinfunction "A_2") (pintype "passive"))
      (node (ref "SW38") (pin "1") (pinfunction "1_1") (pintype "passive"))
    )
    (net (code "63") (name "Net-(D42-A)") (class "Default")
      (node (ref "D42") (pin "2") (pinfunction "A_2") (pintype "passive"))
      (node (ref "SW39") (pin "1") (pinfunction "1_1") (pintype "passive"))
    )
    (net (code "64") (name "Net-(D43-A)") (class "Default")
      (node (ref "D43") (pin "2") (pinfunction "A_2") (pintype "passive"))
      (node (ref "SW40") (pin "1") (pinfunction "1_1") (pintype "passive"))
    )
    (net (code "65") (name "Net-(D44-A)") (class "Default")
      (node (ref "D44") (pin "2") (pinfunction "A_2") (pintype "passive"))
      (node (ref "SW41") (pin "1") (pinfunction "1_1") (pintype "passive"))
    )
    (net (code "66") (name "Net-(D45-A)") (class "Default")
      (node (ref "D45") (pin "2") (pinfunction "A_2") (pintype "passive"))
      (node (ref "SW42") (pin "1") (pinfunction "1_1") (pintype "passive"))
    )
    (net (code "67") (name "Net-(D46-A)") (class "Default")
      (node (ref "D46") (pin "2") (pinfunction "A_2") (pintype "passive"))
      (node (ref "SW43") (pin "1") (pinfunction "1_1") (pintype "passive"))
    )
    (net (code "68") (name "Net-(D47-A)") (class "Default")
      (node (ref "D47") (pin "2") (pinfunction "A_2") (pintype "passive"))
      (node (ref "SW44") (pin "1") (pinfunction "1_1") (pintype "passive"))
    )
    (net (code "69") (name "Net-(D48-A)") (class "Default")
      (node (ref "D48") (pin "2") (pinfunction "A_2") (pintype "passive"))
      (node (ref "SW45") (pin "1") (pinfunction "1_1") (pintype "passive"))
    )
    (net (code "70") (name "Net-(D49-A)") (class "Default")
      (node (ref "D49") (pin "2") (pinfunction "A_2") (pintype "passive"))
      (node (ref "SW46") (pin "1") (pinfunction "1_1") (pintype "passive"))
    )
    (net (code "71") (name "Net-(D50-A)") (class "Default")
      (node (ref "D50") (pin "2") (pinfunction "A_2") (pintype "passive"))
      (node (ref "SW47") (pin "1") (pinfunction "1_1") (pintype "passive"))
    )
    (net (code "72") (name "Net-(D51-A)") (class "Default")
      (node (ref "D51") (pin "2") (pinfunction "A_2") (pintype "passive"))
      (node (ref "SW48") (pin "1") (pinfunction "1_1") (pintype "passive"))
    )
    (net (code "73") (name "Net-(D52-A)") (class "Default")
      (node (ref "D52") (pin "2") (pinfunction "A_2") (pintype "passive"))
      (node (ref "SW49") (pin "1") (pinfunction "1_1") (pintype "passive"))
    )
    (net (code "74") (name "Net-(D53-A)") (class "Default")
      (node (ref "D53") (pin "2") (pinfunction "A_2") (pintype "passive"))
      (node (ref "SW50") (pin "1") (pinfunction "1_1") (pintype "passive"))
    )
    (net (code "75") (name "Net-(D54-A)") (class "Default")
      (node (ref "D54") (pin "2") (pinfunction "A_2") (pintype "passive"))
      (node (ref "SW51") (pin "1") (pinfunction "1_1") (pintype "passive"))
    )
    (net (code "76") (name "Net-(D55-A)") (class "Default")
      (node (ref "D55") (pin "2") (pinfunction "A_2") (pintype "passive"))
      (node (ref "SW52") (pin "1") (pinfunction "1_1") (pintype "passive"))
    )
    (net (code "77") (name "Net-(D56-A)") (class "Default")
      (node (ref "D56") (pin "2") (pinfunction "A_2") (pintype "passive"))
      (node (ref "SW53") (pin "1") (pinfunction "1_1") (pintype "passive"))
    )
    (net (code "78") (name "Net-(D57-A)") (class "Default")
      (node (ref "D57") (pin "2") (pinfunction "A_2") (pintype "passive"))
      (node (ref "SW54") (pin "1") (pinfunction "1_1") (pintype "passive"))
    )
    (net (code "79") (name "Net-(D58-A)") (class "Default")
      (node (ref "D58") (pin "2") (pinfunction "A_2") (pintype "passive"))
      (node (ref "SW55") (pin "1") (pinfunction "1_1") (pintype "passive"))
    )
    (net (code "80") (name "Net-(D59-A)") (class "Default")
      (node (ref "D59") (pin "2") (pinfunction "A_2") (pintype "passive"))
      (node (ref "SW56") (pin "1") (pinfunction "1_1") (pintype "passive"))
    )
    (net (code "81") (name "Net-(D60-A)") (class "Default")
      (node (ref "D60") (pin "2") (pinfunction "A_2") (pintype "passive"))
      (node (ref "SW57") (pin "1") (pinfunction "1_1") (pintype "passive"))
    )
    (net (code "82") (name "Net-(D61-A)") (class "Default")
      (node (ref "D61") (pin "2") (pinfunction "A_2") (pintype "passive"))
      (node (ref "SW58") (pin "1") (pinfunction "1_1") (pintype "passive"))
    )
    (net (code "83") (name "Net-(D62-A)") (class "Default")
      (node (ref "D62") (pin "2") (pinfunction "A_2") (pintype "passive"))
      (node (ref "SW59") (pin "1") (pinfunction "1_1") (pintype "passive"))
    )
    (net (code "84") (name "Net-(D63-A)") (class "Default")
      (node (ref "D63") (pin "2") (pinfunction "A_2") (pintype "passive"))
      (node (ref "SW60") (pin "1") (pinfunction "1_1") (pintype "passive"))
    )
    (net (code "85") (name "Net-(D64-A)") (class "Default")
      (node (ref "D64") (pin "2") (pinfunction "A_2") (pintype "passive"))
      (node (ref "SW61") (pin "1") (pinfunction "1_1") (pintype "passive"))
    )
    (net (code "86") (name "Net-(D65-A)") (class "Default")
      (node (ref "D65") (pin "2") (pinfunction "A_2") (pintype "passive"))
      (node (ref "SW62") (pin "1") (pinfunction "1_1") (pintype "passive"))
    )
    (net (code "87") (name "Net-(D66-A)") (class "Default")
      (node (ref "D66") (pin "2") (pinfunction "A_2") (pintype "passive"))
      (node (ref "SW63") (pin "1") (pinfunction "1_1") (pintype "passive"))
    )
    (net (code "88") (name "Net-(D67-A)") (class "Default")
      (node (ref "D67") (pin "2") (pinfunction "A_2") (pintype "passive"))
      (node (ref "SW64") (pin "1") (pinfunction "1_1") (pintype "passive"))
    )
    (net (code "89") (name "Net-(D68-A)") (class "Default")
      (node (ref "D68") (pin "2") (pinfunction "A_2") (pintype "passive"))
      (node (ref "SW65") (pin "1") (pinfunction "1_1") (pintype "passive"))
    )
    (net (code "90") (name "Net-(D69-A)") (class "Default")
      (node (ref "D69") (pin "2") (pinfunction "A_2") (pintype "passive"))
      (node (ref "SW66") (pin "1") (pinfunction "1_1") (pintype "passive"))
    )
    (net (code "91") (name "Net-(ENC1-CHANNEL_A)") (class "Default")
      (node (ref "ENC1") (pin "A") (pinfunction "CHANNEL_A_A") (pintype "passive"))
      (node (ref "R9") (pin "1") (pinfunction "1_1") (pintype "passive"))
    )
    (net (code "92") (name "Net-(ENC1-CHANNEL_B)") (class "Default")
      (node (ref "ENC1") (pin "B") (pinfunction "CHANNEL_B_B") (pintype "passive"))
      (node (ref "R10") (pin "1") (pinfunction "1_1") (pintype "passive"))
    )
  )
)
